# Puddles_Backplane_FOR_REFERENCE.net
KiCad netlist of a schematic drawn in EAGLE
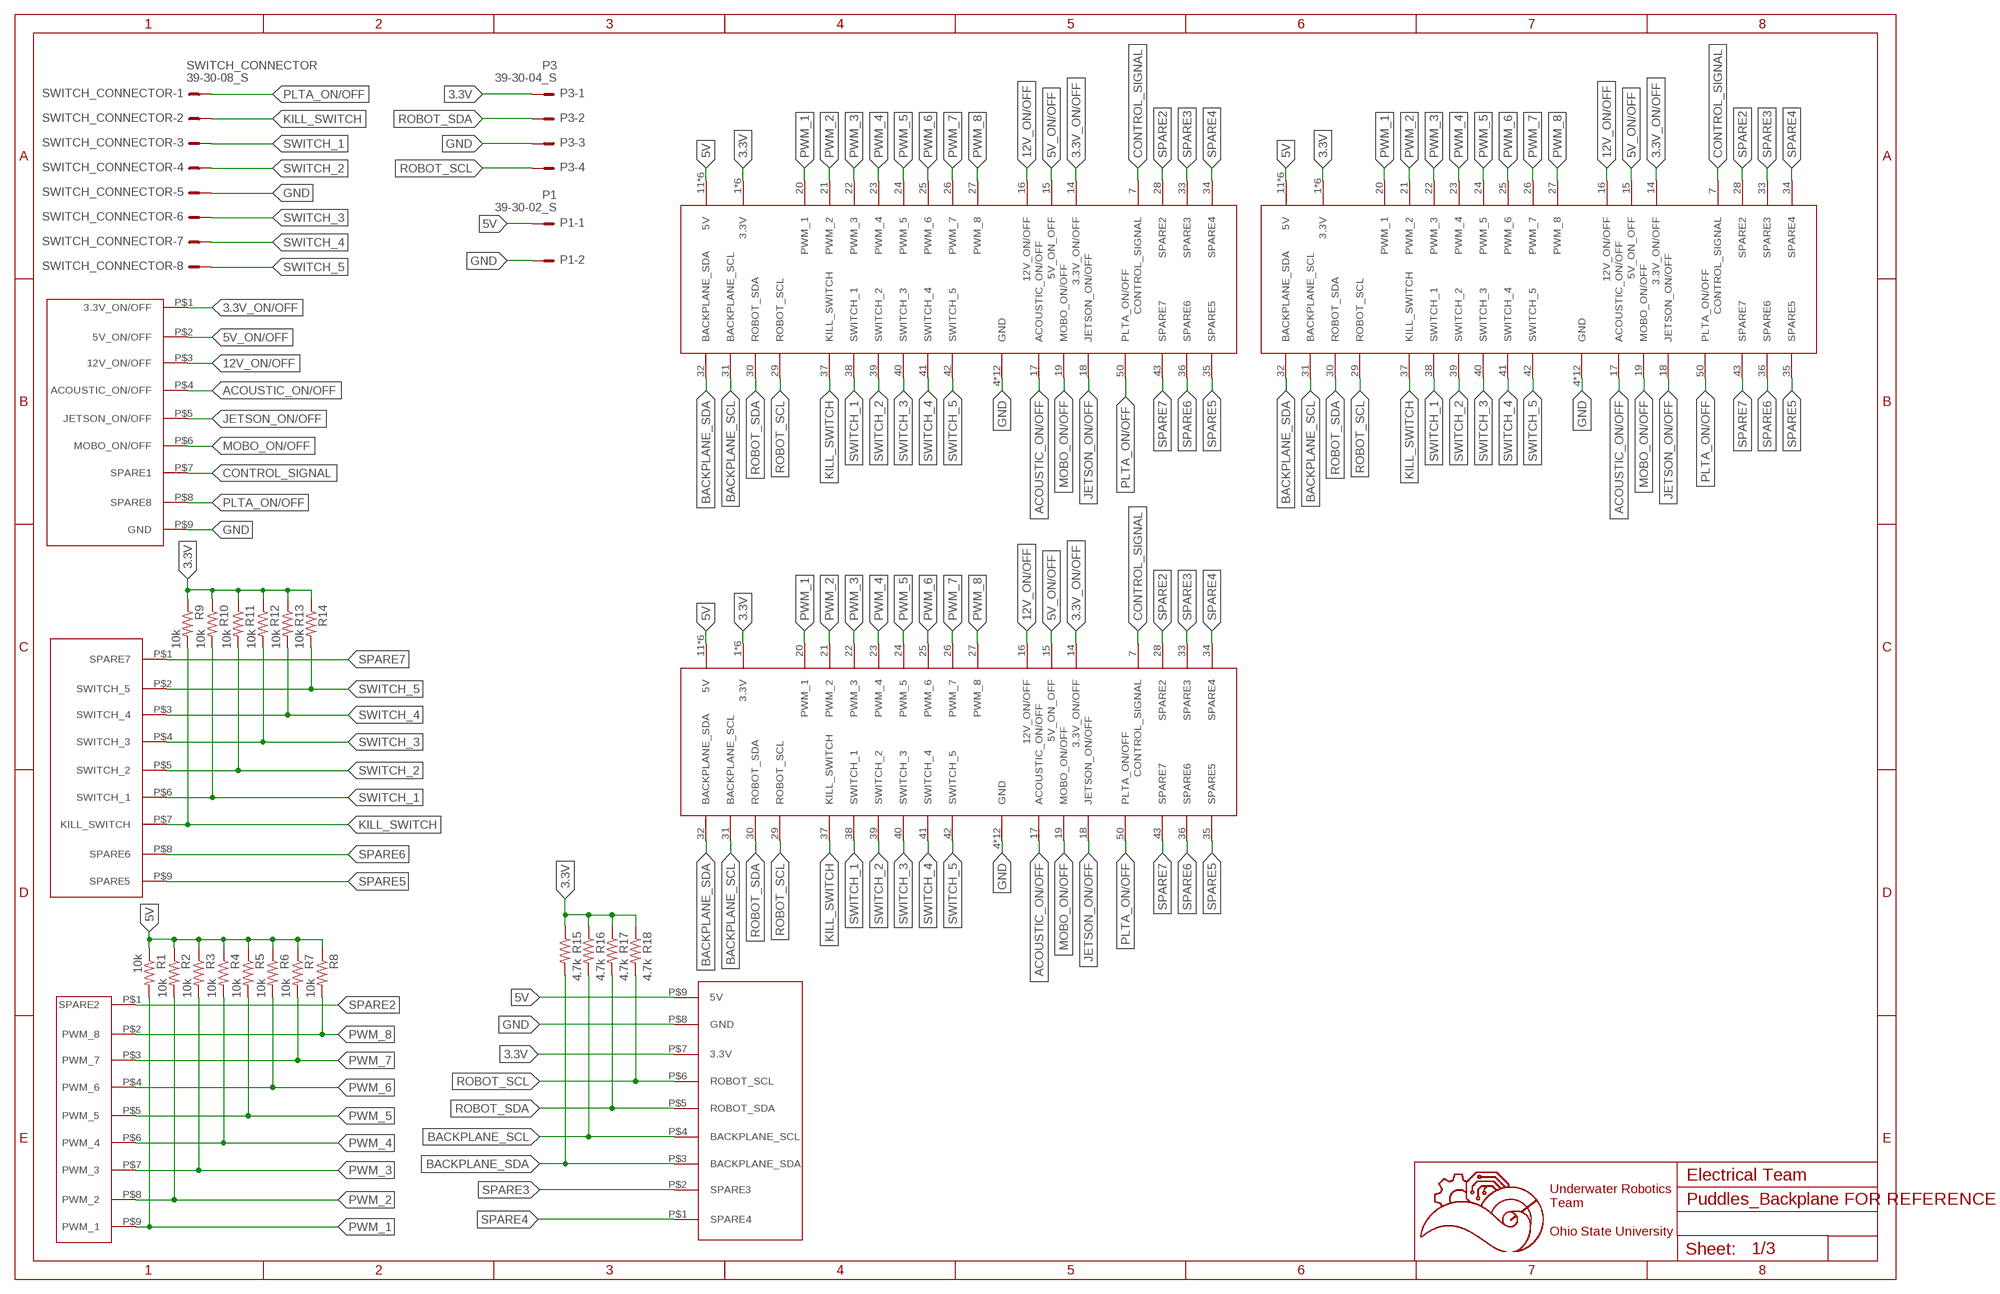
[diagram p0: schematic, sheet 1]
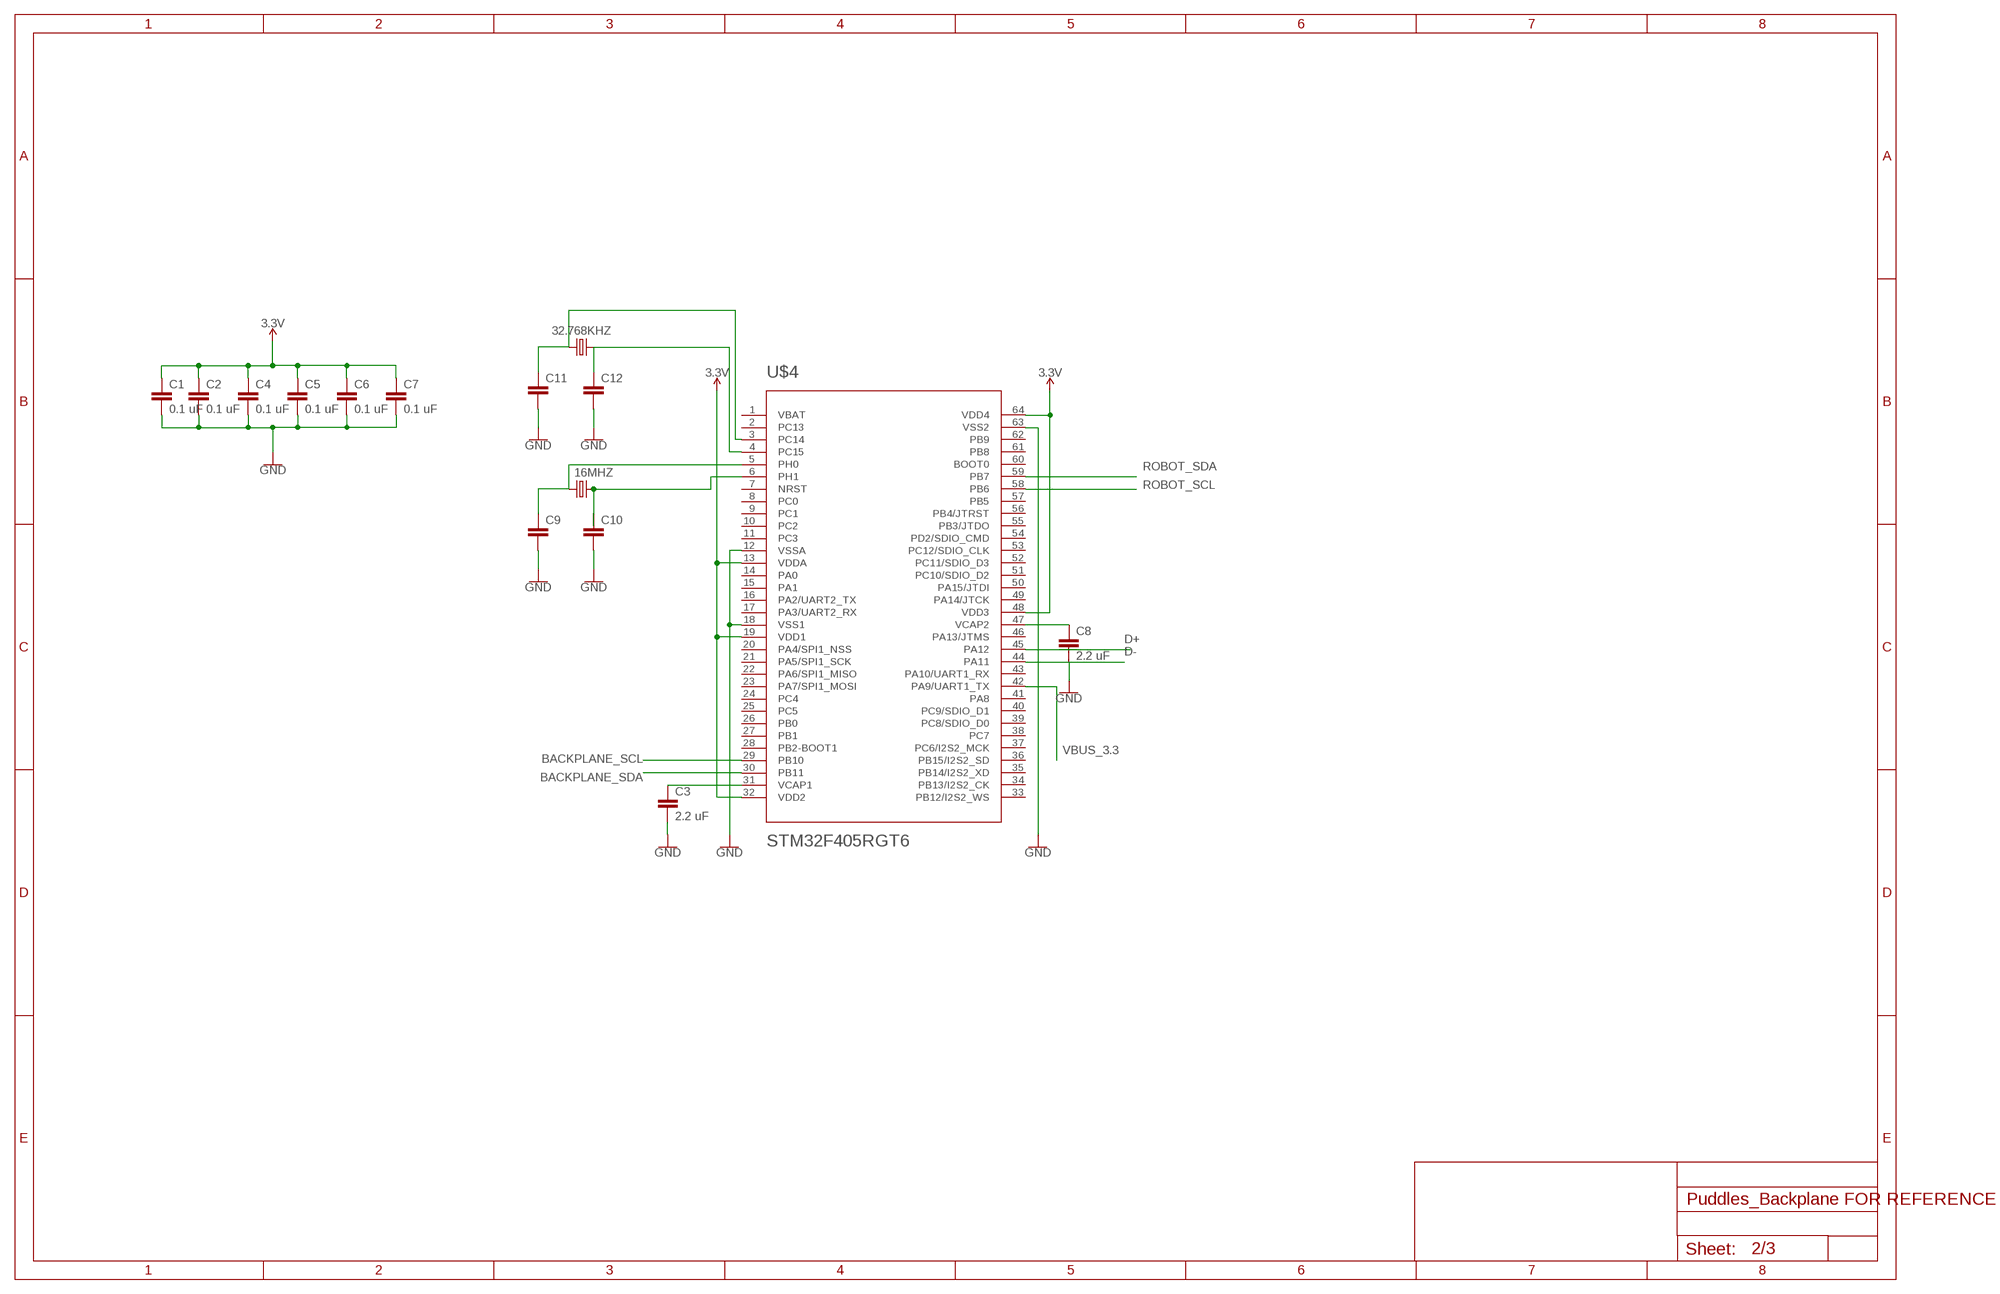
[diagram p1: schematic, sheet 2]
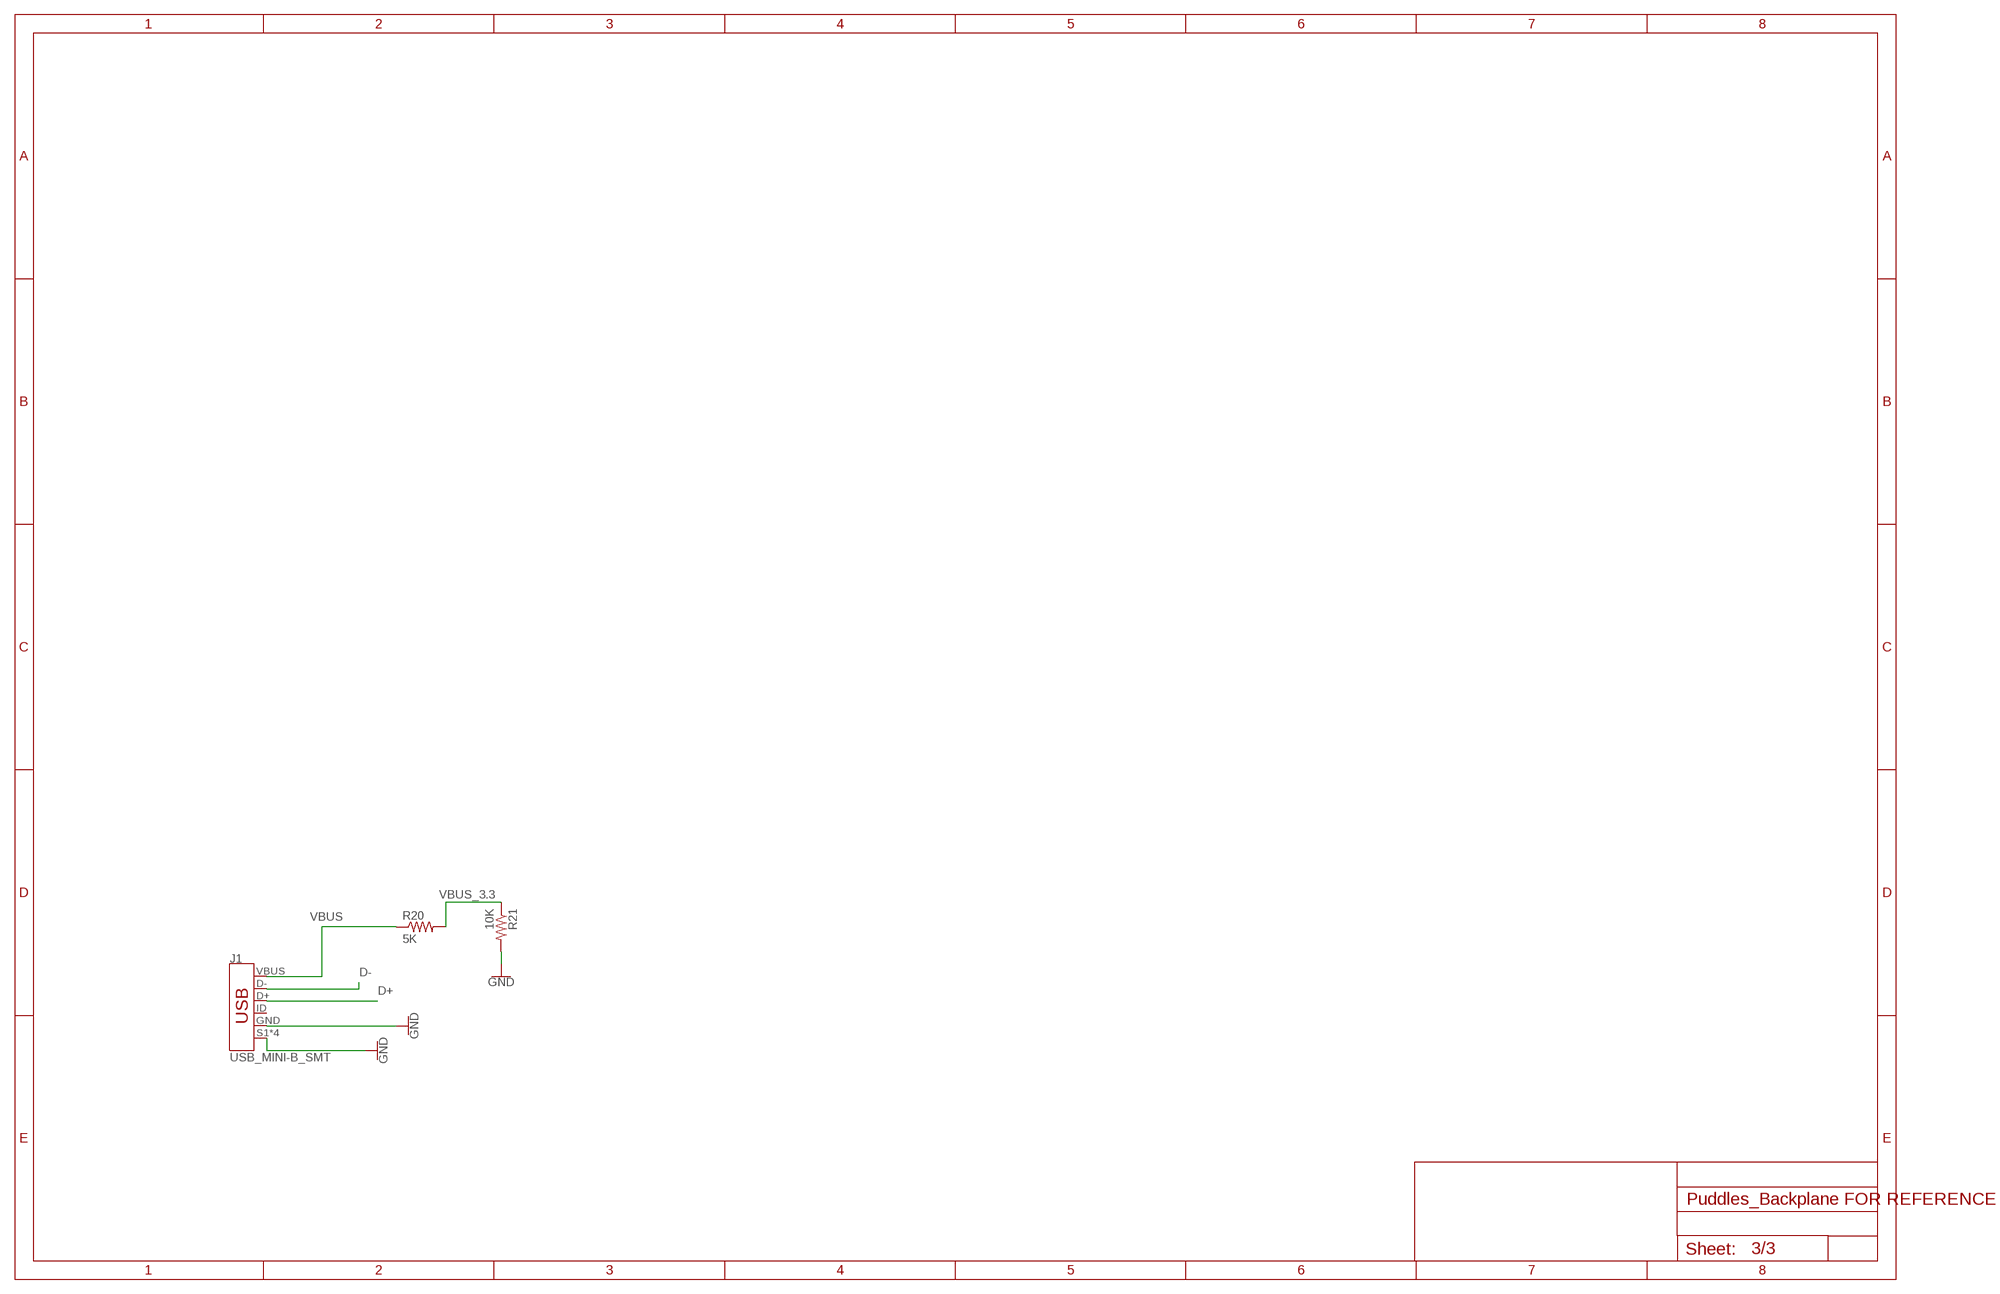
[diagram p2: schematic, sheet 3]

(export (version "E")
  (design (tool "Eeschema 10.0.6"))
  (components
    (comp (ref "J1")
      (value "USB_MINI-B_SMT")
      (footprint "eagle-import:USB-MINIB")
      (libsource (lib "eagle-import") (part "USB_MINI-B_SMT"))
    )
    (comp (ref "R20")
      (value "5K")
      (footprint "eagle-import:R0603")
      (libsource (lib "eagle-import") (part "R-US_R0603"))
    )
    (comp (ref "R21")
      (value "10K")
      (footprint "eagle-import:R0603")
      (libsource (lib "eagle-import") (part "R-US_R0603"))
    )
    (comp (ref "16MHZ")
      (value "CRYSTALPTH-HC49US")
      (footprint "eagle-import:HC49US")
      (libsource (lib "eagle-import") (part "CRYSTALPTH-HC49US"))
    )
    (comp (ref "32.768KHZ")
      (value "CRYSTALPTH-HC49US")
      (footprint "eagle-import:HC49US")
      (libsource (lib "eagle-import") (part "CRYSTALPTH-HC49US"))
    )
    (comp (ref "C1")
      (value "0.1 uF")
      (footprint "eagle-import:C0603")
      (libsource (lib "eagle-import") (part "C-EUC0603"))
    )
    (comp (ref "C2")
      (value "0.1 uF")
      (footprint "eagle-import:C0603")
      (libsource (lib "eagle-import") (part "C-EUC0603"))
    )
    (comp (ref "C3")
      (value "2.2 uF")
      (footprint "eagle-import:C0603")
      (libsource (lib "eagle-import") (part "C-EUC0603"))
    )
    (comp (ref "C4")
      (value "0.1 uF")
      (footprint "eagle-import:C0603")
      (libsource (lib "eagle-import") (part "C-EUC0603"))
    )
    (comp (ref "C5")
      (value "0.1 uF")
      (footprint "eagle-import:C0603")
      (libsource (lib "eagle-import") (part "C-EUC0603"))
    )
    (comp (ref "C6")
      (value "0.1 uF")
      (footprint "eagle-import:C0603")
      (libsource (lib "eagle-import") (part "C-EUC0603"))
    )
    (comp (ref "C7")
      (value "0.1 uF")
      (footprint "eagle-import:C0603")
      (libsource (lib "eagle-import") (part "C-EUC0603"))
    )
    (comp (ref "C8")
      (value "2.2 uF")
      (footprint "eagle-import:C0603")
      (libsource (lib "eagle-import") (part "C-EUC0603"))
    )
    (comp (ref "C9")
      (value "C-EUC0603")
      (footprint "eagle-import:C0603")
      (libsource (lib "eagle-import") (part "C-EUC0603"))
    )
    (comp (ref "C10")
      (value "C-EUC0603")
      (footprint "eagle-import:C0603")
      (libsource (lib "eagle-import") (part "C-EUC0603"))
    )
    (comp (ref "C11")
      (value "C-EUC0603")
      (footprint "eagle-import:C0603")
      (libsource (lib "eagle-import") (part "C-EUC0603"))
    )
    (comp (ref "C12")
      (value "C-EUC0603")
      (footprint "eagle-import:C0603")
      (libsource (lib "eagle-import") (part "C-EUC0603"))
    )
    (comp (ref "U$4")
      (value "STM32F405RGT6")
      (footprint "eagle-import:TQFP64")
      (libsource (lib "eagle-import") (part "STM32F405RG"))
    )
    (comp (ref "P1")
      (value "39-30-02_S")
      (footprint "eagle-import:39-30-_02_")
      (libsource (lib "eagle-import") (part "39-30-?02?_S"))
    )
    (comp (ref "P3")
      (value "39-30-04_S")
      (footprint "eagle-import:39-30-_04_")
      (libsource (lib "eagle-import") (part "39-30-?04?_S"))
    )
    (comp (ref "R1")
      (value "10k")
      (footprint "eagle-import:R0603")
      (libsource (lib "eagle-import") (part "R-US_R0603"))
    )
    (comp (ref "R2")
      (value "10k")
      (footprint "eagle-import:R0603")
      (libsource (lib "eagle-import") (part "R-US_R0603"))
    )
    (comp (ref "R3")
      (value "10k")
      (footprint "eagle-import:R0603")
      (libsource (lib "eagle-import") (part "R-US_R0603"))
    )
    (comp (ref "R4")
      (value "10k")
      (footprint "eagle-import:R0603")
      (libsource (lib "eagle-import") (part "R-US_R0603"))
    )
    (comp (ref "R5")
      (value "10k")
      (footprint "eagle-import:R0603")
      (libsource (lib "eagle-import") (part "R-US_R0603"))
    )
    (comp (ref "R6")
      (value "10k")
      (footprint "eagle-import:R0603")
      (libsource (lib "eagle-import") (part "R-US_R0603"))
    )
    (comp (ref "R7")
      (value "10k")
      (footprint "eagle-import:R0603")
      (libsource (lib "eagle-import") (part "R-US_R0603"))
    )
    (comp (ref "R8")
      (value "10k")
      (footprint "eagle-import:R0603")
      (libsource (lib "eagle-import") (part "R-US_R0603"))
    )
    (comp (ref "R9")
      (value "10k")
      (footprint "eagle-import:R0603")
      (libsource (lib "eagle-import") (part "R-US_R0603"))
    )
    (comp (ref "R10")
      (value "10k")
      (footprint "eagle-import:R0603")
      (libsource (lib "eagle-import") (part "R-US_R0603"))
    )
    (comp (ref "R11")
      (value "10k")
      (footprint "eagle-import:R0603")
      (libsource (lib "eagle-import") (part "R-US_R0603"))
    )
    (comp (ref "R12")
      (value "10k")
      (footprint "eagle-import:R0603")
      (libsource (lib "eagle-import") (part "R-US_R0603"))
    )
    (comp (ref "R13")
      (value "10k")
      (footprint "eagle-import:R0603")
      (libsource (lib "eagle-import") (part "R-US_R0603"))
    )
    (comp (ref "R14")
      (value "10k")
      (footprint "eagle-import:R0603")
      (libsource (lib "eagle-import") (part "R-US_R0603"))
    )
    (comp (ref "R15")
      (value "4.7k")
      (footprint "eagle-import:R0603")
      (libsource (lib "eagle-import") (part "R-US_R0603"))
    )
    (comp (ref "R16")
      (value "4.7k")
      (footprint "eagle-import:R0603")
      (libsource (lib "eagle-import") (part "R-US_R0603"))
    )
    (comp (ref "R17")
      (value "4.7k")
      (footprint "eagle-import:R0603")
      (libsource (lib "eagle-import") (part "R-US_R0603"))
    )
    (comp (ref "R18")
      (value "4.7k")
      (footprint "eagle-import:R0603")
      (libsource (lib "eagle-import") (part "R-US_R0603"))
    )
    (comp (ref "SWITCH_CONNECTOR")
      (value "39-30-08_S")
      (footprint "eagle-import:39-30-_08_")
      (libsource (lib "eagle-import") (part "39-30-?08?_S"))
    )
    (comp (ref "U$1")
      (value "5530843-FEMALE")
      (footprint "eagle-import:5530843-6-BACKPLANEMATE")
      (libsource (lib "eagle-import") (part "5530843-FEMALE"))
    )
    (comp (ref "U$2")
      (value "5530843-FEMALE")
      (footprint "eagle-import:5530843-6-BACKPLANEMATE")
      (libsource (lib "eagle-import") (part "5530843-FEMALE"))
    )
    (comp (ref "U$3")
      (value "5530843-FEMALE")
      (footprint "eagle-import:5530843-6-BACKPLANEMATE")
      (libsource (lib "eagle-import") (part "5530843-FEMALE"))
    )
    (comp (ref "U$5")
      (value "929870-01-09_1")
      (footprint "eagle-import:929852-01-09_1ROW")
      (libsource (lib "eagle-import") (part "929870-01-09_1"))
    )
    (comp (ref "U$6")
      (value "929870-01-09_2")
      (footprint "eagle-import:929852-01-09_1ROW")
      (libsource (lib "eagle-import") (part "929870-01-09_2"))
    )
    (comp (ref "U$7")
      (value "929870-01-09_3")
      (footprint "eagle-import:929852-01-09_1ROW")
      (libsource (lib "eagle-import") (part "929870-01-09_3"))
    )
    (comp (ref "U$8")
      (value "929870-01-09_4")
      (footprint "eagle-import:929852-01-09_1ROW")
      (libsource (lib "eagle-import") (part "929870-01-09_4"))
    )
  )
  (nets
    (net (code "1") (name "3.3V") (class "Default")
      (node (ref "C1") (pin "1") (pinfunction "1_1") (pintype "passive"))
      (node (ref "C2") (pin "1") (pinfunction "1_1") (pintype "passive"))
      (node (ref "C4") (pin "1") (pinfunction "1_1") (pintype "passive"))
      (node (ref "C5") (pin "1") (pinfunction "1_1") (pintype "passive"))
      (node (ref "C6") (pin "1") (pinfunction "1_1") (pintype "passive"))
      (node (ref "C7") (pin "1") (pinfunction "1_1") (pintype "passive"))
      (node (ref "P3") (pin "1") (pinfunction "P_1") (pintype "passive"))
      (node (ref "R10") (pin "1") (pinfunction "1_1") (pintype "passive"))
      (node (ref "R11") (pin "1") (pinfunction "1_1") (pintype "passive"))
      (node (ref "R12") (pin "1") (pinfunction "1_1") (pintype "passive"))
      (node (ref "R13") (pin "1") (pinfunction "1_1") (pintype "passive"))
      (node (ref "R14") (pin "1") (pinfunction "1_1") (pintype "passive"))
      (node (ref "R15") (pin "1") (pinfunction "1_1") (pintype "passive"))
      (node (ref "R16") (pin "1") (pinfunction "1_1") (pintype "passive"))
      (node (ref "R17") (pin "1") (pinfunction "1_1") (pintype "passive"))
      (node (ref "R18") (pin "1") (pinfunction "1_1") (pintype "passive"))
      (node (ref "R9") (pin "1") (pinfunction "1_1") (pintype "passive"))
      (node (ref "U$1") (pin "1") (pinfunction "3.3V_1") (pintype "bidirectional"))
      (node (ref "U$1") (pin "2") (pinfunction "3.3V_2") (pintype "bidirectional"))
      (node (ref "U$1") (pin "3") (pinfunction "3.3V_3") (pintype "bidirectional"))
      (node (ref "U$1") (pin "54") (pinfunction "3.3V_54") (pintype "bidirectional"))
      (node (ref "U$1") (pin "55") (pinfunction "3.3V_55") (pintype "bidirectional"))
      (node (ref "U$1") (pin "56") (pinfunction "3.3V_56") (pintype "bidirectional"))
      (node (ref "U$2") (pin "1") (pinfunction "3.3V_1") (pintype "bidirectional"))
      (node (ref "U$2") (pin "2") (pinfunction "3.3V_2") (pintype "bidirectional"))
      (node (ref "U$2") (pin "3") (pinfunction "3.3V_3") (pintype "bidirectional"))
      (node (ref "U$2") (pin "54") (pinfunction "3.3V_54") (pintype "bidirectional"))
      (node (ref "U$2") (pin "55") (pinfunction "3.3V_55") (pintype "bidirectional"))
      (node (ref "U$2") (pin "56") (pinfunction "3.3V_56") (pintype "bidirectional"))
      (node (ref "U$3") (pin "1") (pinfunction "3.3V_1") (pintype "bidirectional"))
      (node (ref "U$3") (pin "2") (pinfunction "3.3V_2") (pintype "bidirectional"))
      (node (ref "U$3") (pin "3") (pinfunction "3.3V_3") (pintype "bidirectional"))
      (node (ref "U$3") (pin "54") (pinfunction "3.3V_54") (pintype "bidirectional"))
      (node (ref "U$3") (pin "55") (pinfunction "3.3V_55") (pintype "bidirectional"))
      (node (ref "U$3") (pin "56") (pinfunction "3.3V_56") (pintype "bidirectional"))
      (node (ref "U$4") (pin "13") (pinfunction "VDDA_13") (pintype "bidirectional"))
      (node (ref "U$4") (pin "19") (pinfunction "VDD1_19") (pintype "bidirectional"))
      (node (ref "U$4") (pin "32") (pinfunction "VDD2_32") (pintype "bidirectional"))
      (node (ref "U$4") (pin "48") (pinfunction "VDD3_48") (pintype "bidirectional"))
      (node (ref "U$4") (pin "64") (pinfunction "VDD4_64") (pintype "bidirectional"))
      (node (ref "U$8") (pin "P$7") (pinfunction "3.3V_P$7") (pintype "bidirectional"))
    )
    (net (code "2") (name "3.3V_ON{slash}OFF") (class "Default")
      (node (ref "U$1") (pin "14") (pinfunction "3.3V_ON/OFF_14") (pintype "bidirectional"))
      (node (ref "U$2") (pin "14") (pinfunction "3.3V_ON/OFF_14") (pintype "bidirectional"))
      (node (ref "U$3") (pin "14") (pinfunction "3.3V_ON/OFF_14") (pintype "bidirectional"))
      (node (ref "U$7") (pin "P$1") (pinfunction "3.3V_ON/OFF_P$1") (pintype "bidirectional"))
    )
    (net (code "3") (name "5V") (class "Default")
      (node (ref "P1") (pin "1") (pinfunction "P_1") (pintype "passive"))
      (node (ref "R1") (pin "1") (pinfunction "1_1") (pintype "passive"))
      (node (ref "R2") (pin "1") (pinfunction "1_1") (pintype "passive"))
      (node (ref "R3") (pin "1") (pinfunction "1_1") (pintype "passive"))
      (node (ref "R4") (pin "1") (pinfunction "1_1") (pintype "passive"))
      (node (ref "R5") (pin "1") (pinfunction "1_1") (pintype "passive"))
      (node (ref "R6") (pin "1") (pinfunction "1_1") (pintype "passive"))
      (node (ref "R7") (pin "1") (pinfunction "1_1") (pintype "passive"))
      (node (ref "R8") (pin "1") (pinfunction "1_1") (pintype "passive"))
      (node (ref "U$1") (pin "11") (pinfunction "5V_11") (pintype "bidirectional"))
      (node (ref "U$1") (pin "12") (pinfunction "5V_12") (pintype "bidirectional"))
      (node (ref "U$1") (pin "13") (pinfunction "5V_13") (pintype "bidirectional"))
      (node (ref "U$1") (pin "44") (pinfunction "5V_44") (pintype "bidirectional"))
      (node (ref "U$1") (pin "45") (pinfunction "5V_45") (pintype "bidirectional"))
      (node (ref "U$1") (pin "46") (pinfunction "5V_46") (pintype "bidirectional"))
      (node (ref "U$2") (pin "11") (pinfunction "5V_11") (pintype "bidirectional"))
      (node (ref "U$2") (pin "12") (pinfunction "5V_12") (pintype "bidirectional"))
      (node (ref "U$2") (pin "13") (pinfunction "5V_13") (pintype "bidirectional"))
      (node (ref "U$2") (pin "44") (pinfunction "5V_44") (pintype "bidirectional"))
      (node (ref "U$2") (pin "45") (pinfunction "5V_45") (pintype "bidirectional"))
      (node (ref "U$2") (pin "46") (pinfunction "5V_46") (pintype "bidirectional"))
      (node (ref "U$3") (pin "11") (pinfunction "5V_11") (pintype "bidirectional"))
      (node (ref "U$3") (pin "12") (pinfunction "5V_12") (pintype "bidirectional"))
      (node (ref "U$3") (pin "13") (pinfunction "5V_13") (pintype "bidirectional"))
      (node (ref "U$3") (pin "44") (pinfunction "5V_44") (pintype "bidirectional"))
      (node (ref "U$3") (pin "45") (pinfunction "5V_45") (pintype "bidirectional"))
      (node (ref "U$3") (pin "46") (pinfunction "5V_46") (pintype "bidirectional"))
      (node (ref "U$8") (pin "P$9") (pinfunction "5V_P$9") (pintype "bidirectional"))
    )
    (net (code "4") (name "5V_ON{slash}OFF") (class "Default")
      (node (ref "U$1") (pin "15") (pinfunction "5V_ON_OFF_15") (pintype "bidirectional"))
      (node (ref "U$2") (pin "15") (pinfunction "5V_ON_OFF_15") (pintype "bidirectional"))
      (node (ref "U$3") (pin "15") (pinfunction "5V_ON_OFF_15") (pintype "bidirectional"))
      (node (ref "U$7") (pin "P$2") (pinfunction "5V_ON/OFF_P$2") (pintype "bidirectional"))
    )
    (net (code "5") (name "12V_ON{slash}OFF") (class "Default")
      (node (ref "U$1") (pin "16") (pinfunction "12V_ON/OFF_16") (pintype "bidirectional"))
      (node (ref "U$2") (pin "16") (pinfunction "12V_ON/OFF_16") (pintype "bidirectional"))
      (node (ref "U$3") (pin "16") (pinfunction "12V_ON/OFF_16") (pintype "bidirectional"))
      (node (ref "U$7") (pin "P$3") (pinfunction "12V_ON/OFF_P$3") (pintype "bidirectional"))
    )
    (net (code "6") (name "ACOUSTIC_ON{slash}OFF") (class "Default")
      (node (ref "U$1") (pin "17") (pinfunction "ACOUSTIC_ON/OFF_17") (pintype "bidirectional"))
      (node (ref "U$2") (pin "17") (pinfunction "ACOUSTIC_ON/OFF_17") (pintype "bidirectional"))
      (node (ref "U$3") (pin "17") (pinfunction "ACOUSTIC_ON/OFF_17") (pintype "bidirectional"))
      (node (ref "U$7") (pin "P$4") (pinfunction "ACOUSTIC_ON/OFF_P$4") (pintype "bidirectional"))
    )
    (net (code "7") (name "BACKPLANE_SCL") (class "Default")
      (node (ref "R16") (pin "2") (pinfunction "2_2") (pintype "passive"))
      (node (ref "U$1") (pin "31") (pinfunction "BACKPLANE_SCL_31") (pintype "bidirectional"))
      (node (ref "U$2") (pin "31") (pinfunction "BACKPLANE_SCL_31") (pintype "bidirectional"))
      (node (ref "U$3") (pin "31") (pinfunction "BACKPLANE_SCL_31") (pintype "bidirectional"))
      (node (ref "U$4") (pin "29") (pinfunction "PB10_29") (pintype "bidirectional"))
      (node (ref "U$8") (pin "P$4") (pinfunction "BACKPLANE_SCL_P$4") (pintype "bidirectional"))
    )
    (net (code "8") (name "BACKPLANE_SDA") (class "Default")
      (node (ref "R15") (pin "2") (pinfunction "2_2") (pintype "passive"))
      (node (ref "U$1") (pin "32") (pinfunction "BACKPLANE_SDA_32") (pintype "bidirectional"))
      (node (ref "U$2") (pin "32") (pinfunction "BACKPLANE_SDA_32") (pintype "bidirectional"))
      (node (ref "U$3") (pin "32") (pinfunction "BACKPLANE_SDA_32") (pintype "bidirectional"))
      (node (ref "U$4") (pin "30") (pinfunction "PB11_30") (pintype "bidirectional"))
      (node (ref "U$8") (pin "P$3") (pinfunction "BACKPLANE_SDA_P$3") (pintype "bidirectional"))
    )
    (net (code "9") (name "CONTROL_SIGNAL") (class "Default")
      (node (ref "U$1") (pin "7") (pinfunction "CONTROL_SIGNAL_7") (pintype "bidirectional"))
      (node (ref "U$2") (pin "7") (pinfunction "CONTROL_SIGNAL_7") (pintype "bidirectional"))
      (node (ref "U$3") (pin "7") (pinfunction "CONTROL_SIGNAL_7") (pintype "bidirectional"))
      (node (ref "U$7") (pin "P$7") (pinfunction "SPARE1_P$7") (pintype "bidirectional"))
    )
    (net (code "10") (name "D+") (class "Default")
      (node (ref "J1") (pin "D+") (pinfunction "D+_D+") (pintype "bidirectional"))
      (node (ref "U$4") (pin "45") (pinfunction "PA12_45") (pintype "bidirectional"))
    )
    (net (code "11") (name "D-") (class "Default")
      (node (ref "J1") (pin "D-") (pinfunction "D-_D-") (pintype "bidirectional"))
      (node (ref "U$4") (pin "44") (pinfunction "PA11_44") (pintype "bidirectional"))
    )
    (net (code "12") (name "GND") (class "Default")
      (node (ref "C1") (pin "2") (pinfunction "2_2") (pintype "passive"))
      (node (ref "C10") (pin "2") (pinfunction "2_2") (pintype "passive"))
      (node (ref "C11") (pin "2") (pinfunction "2_2") (pintype "passive"))
      (node (ref "C12") (pin "2") (pinfunction "2_2") (pintype "passive"))
      (node (ref "C2") (pin "2") (pinfunction "2_2") (pintype "passive"))
      (node (ref "C3") (pin "2") (pinfunction "2_2") (pintype "passive"))
      (node (ref "C4") (pin "2") (pinfunction "2_2") (pintype "passive"))
      (node (ref "C5") (pin "2") (pinfunction "2_2") (pintype "passive"))
      (node (ref "C6") (pin "2") (pinfunction "2_2") (pintype "passive"))
      (node (ref "C7") (pin "2") (pinfunction "2_2") (pintype "passive"))
      (node (ref "C8") (pin "2") (pinfunction "2_2") (pintype "passive"))
      (node (ref "C9") (pin "2") (pinfunction "2_2") (pintype "passive"))
      (node (ref "J1") (pin "GND") (pinfunction "GND_GND") (pintype "power_in"))
      (node (ref "J1") (pin "S1") (pinfunction "SHIELD_S1") (pintype "bidirectional"))
      (node (ref "J1") (pin "S2") (pinfunction "SHIELD_S2") (pintype "bidirectional"))
      (node (ref "J1") (pin "S3") (pinfunction "SHIELD_S3") (pintype "bidirectional"))
      (node (ref "J1") (pin "S4") (pinfunction "SHIELD_S4") (pintype "bidirectional"))
      (node (ref "P1") (pin "2") (pinfunction "P_2") (pintype "passive"))
      (node (ref "P3") (pin "3") (pinfunction "P_3") (pintype "passive"))
      (node (ref "R21") (pin "2") (pinfunction "2_2") (pintype "passive"))
      (node (ref "SWITCH_CONNECTOR") (pin "5") (pinfunction "P_5") (pintype "passive"))
      (node (ref "U$1") (pin "10") (pinfunction "GND_10") (pintype "bidirectional"))
      (node (ref "U$1") (pin "4") (pinfunction "GND_4") (pintype "bidirectional"))
      (node (ref "U$1") (pin "47") (pinfunction "GND_47") (pintype "bidirectional"))
      (node (ref "U$1") (pin "48") (pinfunction "GND_48") (pintype "bidirectional"))
      (node (ref "U$1") (pin "49") (pinfunction "GND_49") (pintype "bidirectional"))
      (node (ref "U$1") (pin "5") (pinfunction "GND_5") (pintype "bidirectional"))
      (node (ref "U$1") (pin "51") (pinfunction "GND_51") (pintype "bidirectional"))
      (node (ref "U$1") (pin "52") (pinfunction "GND_52") (pintype "bidirectional"))
      (node (ref "U$1") (pin "53") (pinfunction "GND_53") (pintype "bidirectional"))
      (node (ref "U$1") (pin "6") (pinfunction "GND_6") (pintype "bidirectional"))
      (node (ref "U$1") (pin "8") (pinfunction "GND_8") (pintype "bidirectional"))
      (node (ref "U$1") (pin "9") (pinfunction "GND_9") (pintype "bidirectional"))
      (node (ref "U$2") (pin "10") (pinfunction "GND_10") (pintype "bidirectional"))
      (node (ref "U$2") (pin "4") (pinfunction "GND_4") (pintype "bidirectional"))
      (node (ref "U$2") (pin "47") (pinfunction "GND_47") (pintype "bidirectional"))
      (node (ref "U$2") (pin "48") (pinfunction "GND_48") (pintype "bidirectional"))
      (node (ref "U$2") (pin "49") (pinfunction "GND_49") (pintype "bidirectional"))
      (node (ref "U$2") (pin "5") (pinfunction "GND_5") (pintype "bidirectional"))
      (node (ref "U$2") (pin "51") (pinfunction "GND_51") (pintype "bidirectional"))
      (node (ref "U$2") (pin "52") (pinfunction "GND_52") (pintype "bidirectional"))
      (node (ref "U$2") (pin "53") (pinfunction "GND_53") (pintype "bidirectional"))
      (node (ref "U$2") (pin "6") (pinfunction "GND_6") (pintype "bidirectional"))
      (node (ref "U$2") (pin "8") (pinfunction "GND_8") (pintype "bidirectional"))
      (node (ref "U$2") (pin "9") (pinfunction "GND_9") (pintype "bidirectional"))
      (node (ref "U$3") (pin "10") (pinfunction "GND_10") (pintype "bidirectional"))
      (node (ref "U$3") (pin "4") (pinfunction "GND_4") (pintype "bidirectional"))
      (node (ref "U$3") (pin "47") (pinfunction "GND_47") (pintype "bidirectional"))
      (node (ref "U$3") (pin "48") (pinfunction "GND_48") (pintype "bidirectional"))
      (node (ref "U$3") (pin "49") (pinfunction "GND_49") (pintype "bidirectional"))
      (node (ref "U$3") (pin "5") (pinfunction "GND_5") (pintype "bidirectional"))
      (node (ref "U$3") (pin "51") (pinfunction "GND_51") (pintype "bidirectional"))
      (node (ref "U$3") (pin "52") (pinfunction "GND_52") (pintype "bidirectional"))
      (node (ref "U$3") (pin "53") (pinfunction "GND_53") (pintype "bidirectional"))
      (node (ref "U$3") (pin "6") (pinfunction "GND_6") (pintype "bidirectional"))
      (node (ref "U$3") (pin "8") (pinfunction "GND_8") (pintype "bidirectional"))
      (node (ref "U$3") (pin "9") (pinfunction "GND_9") (pintype "bidirectional"))
      (node (ref "U$4") (pin "12") (pinfunction "VSSA_12") (pintype "bidirectional"))
      (node (ref "U$4") (pin "18") (pinfunction "VSS1_18") (pintype "bidirectional"))
      (node (ref "U$4") (pin "63") (pinfunction "VSS2_63") (pintype "bidirectional"))
      (node (ref "U$7") (pin "P$9") (pinfunction "GND_P$9") (pintype "bidirectional"))
      (node (ref "U$8") (pin "P$8") (pinfunction "GND_P$8") (pintype "bidirectional"))
    )
    (net (code "13") (name "JETSON_ON{slash}OFF") (class "Default")
      (node (ref "U$1") (pin "18") (pinfunction "JETSON_ON/OFF_18") (pintype "bidirectional"))
      (node (ref "U$2") (pin "18") (pinfunction "JETSON_ON/OFF_18") (pintype "bidirectional"))
      (node (ref "U$3") (pin "18") (pinfunction "JETSON_ON/OFF_18") (pintype "bidirectional"))
      (node (ref "U$7") (pin "P$5") (pinfunction "JETSON_ON/OFF_P$5") (pintype "bidirectional"))
    )
    (net (code "14") (name "KILL_SWITCH") (class "Default")
      (node (ref "R9") (pin "2") (pinfunction "2_2") (pintype "passive"))
      (node (ref "SWITCH_CONNECTOR") (pin "2") (pinfunction "P_2") (pintype "passive"))
      (node (ref "U$1") (pin "37") (pinfunction "KILL_SWITCH_37") (pintype "output"))
      (node (ref "U$2") (pin "37") (pinfunction "KILL_SWITCH_37") (pintype "output"))
      (node (ref "U$3") (pin "37") (pinfunction "KILL_SWITCH_37") (pintype "output"))
      (node (ref "U$5") (pin "P$7") (pinfunction "KILL_SWITCH_P$7") (pintype "bidirectional"))
    )
    (net (code "15") (name "MOBO_ON{slash}OFF") (class "Default")
      (node (ref "U$1") (pin "19") (pinfunction "MOBO_ON/OFF_19") (pintype "bidirectional"))
      (node (ref "U$2") (pin "19") (pinfunction "MOBO_ON/OFF_19") (pintype "bidirectional"))
      (node (ref "U$3") (pin "19") (pinfunction "MOBO_ON/OFF_19") (pintype "bidirectional"))
      (node (ref "U$7") (pin "P$6") (pinfunction "MOBO_ON/OFF_P$6") (pintype "bidirectional"))
    )
    (net (code "16") (name "Net-(U$4-PC14)") (class "Default")
      (node (ref "32.768KHZ") (pin "1") (pinfunction "1_1") (pintype "passive"))
      (node (ref "C11") (pin "1") (pinfunction "1_1") (pintype "passive"))
      (node (ref "U$4") (pin "3") (pinfunction "PC14_3") (pintype "bidirectional"))
    )
    (net (code "17") (name "Net-(U$4-PC15)") (class "Default")
      (node (ref "32.768KHZ") (pin "2") (pinfunction "2_2") (pintype "passive"))
      (node (ref "C12") (pin "1") (pinfunction "1_1") (pintype "passive"))
      (node (ref "U$4") (pin "4") (pinfunction "PC15_4") (pintype "bidirectional"))
    )
    (net (code "18") (name "Net-(U$4-PH0)") (class "Default")
      (node (ref "16MHZ") (pin "1") (pinfunction "1_1") (pintype "passive"))
      (node (ref "C9") (pin "1") (pinfunction "1_1") (pintype "passive"))
      (node (ref "U$4") (pin "5") (pinfunction "PH0_5") (pintype "bidirectional"))
    )
    (net (code "19") (name "Net-(U$4-PH1)") (class "Default")
      (node (ref "16MHZ") (pin "2") (pinfunction "2_2") (pintype "passive"))
      (node (ref "C10") (pin "1") (pinfunction "1_1") (pintype "passive"))
      (node (ref "U$4") (pin "6") (pinfunction "PH1_6") (pintype "bidirectional"))
    )
    (net (code "20") (name "Net-(U$4-VCAP1)") (class "Default")
      (node (ref "C3") (pin "1") (pinfunction "1_1") (pintype "passive"))
      (node (ref "U$4") (pin "31") (pinfunction "VCAP1_31") (pintype "bidirectional"))
    )
    (net (code "21") (name "Net-(U$4-VCAP2)") (class "Default")
      (node (ref "C8") (pin "1") (pinfunction "1_1") (pintype "passive"))
      (node (ref "U$4") (pin "47") (pinfunction "VCAP2_47") (pintype "bidirectional"))
    )
    (net (code "22") (name "PLTA_ON{slash}OFF") (class "Default")
      (node (ref "SWITCH_CONNECTOR") (pin "1") (pinfunction "P_1") (pintype "passive"))
      (node (ref "U$1") (pin "50") (pinfunction "PLTA_ON/OFF_50") (pintype "bidirectional"))
      (node (ref "U$2") (pin "50") (pinfunction "PLTA_ON/OFF_50") (pintype "bidirectional"))
      (node (ref "U$3") (pin "50") (pinfunction "PLTA_ON/OFF_50") (pintype "bidirectional"))
      (node (ref "U$7") (pin "P$8") (pinfunction "SPARE8_P$8") (pintype "bidirectional"))
    )
    (net (code "23") (name "PWM_1") (class "Default")
      (node (ref "R1") (pin "2") (pinfunction "2_2") (pintype "passive"))
      (node (ref "U$1") (pin "20") (pinfunction "PWM_1_20") (pintype "bidirectional"))
      (node (ref "U$2") (pin "20") (pinfunction "PWM_1_20") (pintype "bidirectional"))
      (node (ref "U$3") (pin "20") (pinfunction "PWM_1_20") (pintype "bidirectional"))
      (node (ref "U$6") (pin "P$9") (pinfunction "PWM_1_P$9") (pintype "bidirectional"))
    )
    (net (code "24") (name "PWM_2") (class "Default")
      (node (ref "R2") (pin "2") (pinfunction "2_2") (pintype "passive"))
      (node (ref "U$1") (pin "21") (pinfunction "PWM_2_21") (pintype "bidirectional"))
      (node (ref "U$2") (pin "21") (pinfunction "PWM_2_21") (pintype "bidirectional"))
      (node (ref "U$3") (pin "21") (pinfunction "PWM_2_21") (pintype "bidirectional"))
      (node (ref "U$6") (pin "P$8") (pinfunction "PWM_2_P$8") (pintype "bidirectional"))
    )
    (net (code "25") (name "PWM_3") (class "Default")
      (node (ref "R3") (pin "2") (pinfunction "2_2") (pintype "passive"))
      (node (ref "U$1") (pin "22") (pinfunction "PWM_3_22") (pintype "bidirectional"))
      (node (ref "U$2") (pin "22") (pinfunction "PWM_3_22") (pintype "bidirectional"))
      (node (ref "U$3") (pin "22") (pinfunction "PWM_3_22") (pintype "bidirectional"))
      (node (ref "U$6") (pin "P$7") (pinfunction "PWM_3_P$7") (pintype "bidirectional"))
    )
    (net (code "26") (name "PWM_4") (class "Default")
      (node (ref "R4") (pin "2") (pinfunction "2_2") (pintype "passive"))
      (node (ref "U$1") (pin "23") (pinfunction "PWM_4_23") (pintype "bidirectional"))
      (node (ref "U$2") (pin "23") (pinfunction "PWM_4_23") (pintype "bidirectional"))
      (node (ref "U$3") (pin "23") (pinfunction "PWM_4_23") (pintype "bidirectional"))
      (node (ref "U$6") (pin "P$6") (pinfunction "PWM_4_P$6") (pintype "bidirectional"))
    )
    (net (code "27") (name "PWM_5") (class "Default")
      (node (ref "R5") (pin "2") (pinfunction "2_2") (pintype "passive"))
      (node (ref "U$1") (pin "24") (pinfunction "PWM_5_24") (pintype "bidirectional"))
      (node (ref "U$2") (pin "24") (pinfunction "PWM_5_24") (pintype "bidirectional"))
      (node (ref "U$3") (pin "24") (pinfunction "PWM_5_24") (pintype "bidirectional"))
      (node (ref "U$6") (pin "P$5") (pinfunction "PWM_5_P$5") (pintype "bidirectional"))
    )
    (net (code "28") (name "PWM_6") (class "Default")
      (node (ref "R6") (pin "2") (pinfunction "2_2") (pintype "passive"))
      (node (ref "U$1") (pin "25") (pinfunction "PWM_6_25") (pintype "bidirectional"))
      (node (ref "U$2") (pin "25") (pinfunction "PWM_6_25") (pintype "bidirectional"))
      (node (ref "U$3") (pin "25") (pinfunction "PWM_6_25") (pintype "bidirectional"))
      (node (ref "U$6") (pin "P$4") (pinfunction "PWM_6_P$4") (pintype "bidirectional"))
    )
    (net (code "29") (name "PWM_7") (class "Default")
      (node (ref "R7") (pin "2") (pinfunction "2_2") (pintype "passive"))
      (node (ref "U$1") (pin "26") (pinfunction "PWM_7_26") (pintype "bidirectional"))
      (node (ref "U$2") (pin "26") (pinfunction "PWM_7_26") (pintype "bidirectional"))
      (node (ref "U$3") (pin "26") (pinfunction "PWM_7_26") (pintype "bidirectional"))
      (node (ref "U$6") (pin "P$3") (pinfunction "PWM_7_P$3") (pintype "bidirectional"))
    )
    (net (code "30") (name "PWM_8") (class "Default")
      (node (ref "R8") (pin "2") (pinfunction "2_2") (pintype "passive"))
      (node (ref "U$1") (pin "27") (pinfunction "PWM_8_27") (pintype "bidirectional"))
      (node (ref "U$2") (pin "27") (pinfunction "PWM_8_27") (pintype "bidirectional"))
      (node (ref "U$3") (pin "27") (pinfunction "PWM_8_27") (pintype "bidirectional"))
      (node (ref "U$6") (pin "P$2") (pinfunction "PWM_8_P$2") (pintype "bidirectional"))
    )
    (net (code "31") (name "ROBOT_SCL") (class "Default")
      (node (ref "P3") (pin "4") (pinfunction "P_4") (pintype "passive"))
      (node (ref "R18") (pin "2") (pinfunction "2_2") (pintype "passive"))
      (node (ref "U$1") (pin "29") (pinfunction "ROBOT_SCL_29") (pintype "bidirectional"))
      (node (ref "U$2") (pin "29") (pinfunction "ROBOT_SCL_29") (pintype "bidirectional"))
      (node (ref "U$3") (pin "29") (pinfunction "ROBOT_SCL_29") (pintype "bidirectional"))
      (node (ref "U$4") (pin "58") (pinfunction "PB6_58") (pintype "bidirectional"))
      (node (ref "U$8") (pin "P$6") (pinfunction "ROBOT_SCL_P$6") (pintype "bidirectional"))
    )
    (net (code "32") (name "ROBOT_SDA") (class "Default")
      (node (ref "P3") (pin "2") (pinfunction "P_2") (pintype "passive"))
      (node (ref "R17") (pin "2") (pinfunction "2_2") (pintype "passive"))
      (node (ref "U$1") (pin "30") (pinfunction "ROBOT_SDA_30") (pintype "bidirectional"))
      (node (ref "U$2") (pin "30") (pinfunction "ROBOT_SDA_30") (pintype "bidirectional"))
      (node (ref "U$3") (pin "30") (pinfunction "ROBOT_SDA_30") (pintype "bidirectional"))
      (node (ref "U$4") (pin "59") (pinfunction "PB7_59") (pintype "bidirectional"))
      (node (ref "U$8") (pin "P$5") (pinfunction "ROBOT_SDA_P$5") (pintype "bidirectional"))
    )
    (net (code "33") (name "SPARE2") (class "Default")
      (node (ref "U$1") (pin "28") (pinfunction "SPARE2_28") (pintype "bidirectional"))
      (node (ref "U$2") (pin "28") (pinfunction "SPARE2_28") (pintype "bidirectional"))
      (node (ref "U$3") (pin "28") (pinfunction "SPARE2_28") (pintype "bidirectional"))
      (node (ref "U$6") (pin "P$1") (pinfunction "SPARE2_P$1") (pintype "bidirectional"))
    )
    (net (code "34") (name "SPARE3") (class "Default")
      (node (ref "U$1") (pin "33") (pinfunction "SPARE3_33") (pintype "bidirectional"))
      (node (ref "U$2") (pin "33") (pinfunction "SPARE3_33") (pintype "bidirectional"))
      (node (ref "U$3") (pin "33") (pinfunction "SPARE3_33") (pintype "bidirectional"))
      (node (ref "U$8") (pin "P$2") (pinfunction "SPARE3_P$2") (pintype "bidirectional"))
    )
    (net (code "35") (name "SPARE4") (class "Default")
      (node (ref "U$1") (pin "34") (pinfunction "SPARE4_34") (pintype "bidirectional"))
      (node (ref "U$2") (pin "34") (pinfunction "SPARE4_34") (pintype "bidirectional"))
      (node (ref "U$3") (pin "34") (pinfunction "SPARE4_34") (pintype "bidirectional"))
      (node (ref "U$8") (pin "P$1") (pinfunction "SPARE4_P$1") (pintype "bidirectional"))
    )
    (net (code "36") (name "SPARE5") (class "Default")
      (node (ref "U$1") (pin "35") (pinfunction "SPARE5_35") (pintype "bidirectional"))
      (node (ref "U$2") (pin "35") (pinfunction "SPARE5_35") (pintype "bidirectional"))
      (node (ref "U$3") (pin "35") (pinfunction "SPARE5_35") (pintype "bidirectional"))
      (node (ref "U$5") (pin "P$9") (pinfunction "SPARE5_P$9") (pintype "bidirectional"))
    )
    (net (code "37") (name "SPARE6") (class "Default")
      (node (ref "U$1") (pin "36") (pinfunction "SPARE6_36") (pintype "bidirectional"))
      (node (ref "U$2") (pin "36") (pinfunction "SPARE6_36") (pintype "bidirectional"))
      (node (ref "U$3") (pin "36") (pinfunction "SPARE6_36") (pintype "bidirectional"))
      (node (ref "U$5") (pin "P$8") (pinfunction "SPARE6_P$8") (pintype "bidirectional"))
    )
    (net (code "38") (name "SPARE7") (class "Default")
      (node (ref "U$1") (pin "43") (pinfunction "SPARE7_43") (pintype "bidirectional"))
      (node (ref "U$2") (pin "43") (pinfunction "SPARE7_43") (pintype "bidirectional"))
      (node (ref "U$3") (pin "43") (pinfunction "SPARE7_43") (pintype "bidirectional"))
      (node (ref "U$5") (pin "P$1") (pinfunction "SPARE7_P$1") (pintype "bidirectional"))
    )
    (net (code "39") (name "SWITCH_1") (class "Default")
      (node (ref "R10") (pin "2") (pinfunction "2_2") (pintype "passive"))
      (node (ref "SWITCH_CONNECTOR") (pin "3") (pinfunction "P_3") (pintype "passive"))
      (node (ref "U$1") (pin "38") (pinfunction "SWITCH_1_38") (pintype "output"))
      (node (ref "U$2") (pin "38") (pinfunction "SWITCH_1_38") (pintype "output"))
      (node (ref "U$3") (pin "38") (pinfunction "SWITCH_1_38") (pintype "output"))
      (node (ref "U$5") (pin "P$6") (pinfunction "SWITCH_1_P$6") (pintype "bidirectional"))
    )
    (net (code "40") (name "SWITCH_2") (class "Default")
      (node (ref "R11") (pin "2") (pinfunction "2_2") (pintype "passive"))
      (node (ref "SWITCH_CONNECTOR") (pin "4") (pinfunction "P_4") (pintype "passive"))
      (node (ref "U$1") (pin "39") (pinfunction "SWITCH_2_39") (pintype "output"))
      (node (ref "U$2") (pin "39") (pinfunction "SWITCH_2_39") (pintype "output"))
      (node (ref "U$3") (pin "39") (pinfunction "SWITCH_2_39") (pintype "output"))
      (node (ref "U$5") (pin "P$5") (pinfunction "SWITCH_2_P$5") (pintype "bidirectional"))
    )
    (net (code "41") (name "SWITCH_3") (class "Default")
      (node (ref "R12") (pin "2") (pinfunction "2_2") (pintype "passive"))
      (node (ref "SWITCH_CONNECTOR") (pin "6") (pinfunction "P_6") (pintype "passive"))
      (node (ref "U$1") (pin "40") (pinfunction "SWITCH_3_40") (pintype "output"))
      (node (ref "U$2") (pin "40") (pinfunction "SWITCH_3_40") (pintype "output"))
      (node (ref "U$3") (pin "40") (pinfunction "SWITCH_3_40") (pintype "output"))
      (node (ref "U$5") (pin "P$4") (pinfunction "SWITCH_3_P$4") (pintype "bidirectional"))
    )
    (net (code "42") (name "SWITCH_4") (class "Default")
      (node (ref "R13") (pin "2") (pinfunction "2_2") (pintype "passive"))
      (node (ref "SWITCH_CONNECTOR") (pin "7") (pinfunction "P_7") (pintype "passive"))
      (node (ref "U$1") (pin "41") (pinfunction "SWITCH_4_41") (pintype "output"))
      (node (ref "U$2") (pin "41") (pinfunction "SWITCH_4_41") (pintype "output"))
      (node (ref "U$3") (pin "41") (pinfunction "SWITCH_4_41") (pintype "output"))
      (node (ref "U$5") (pin "P$3") (pinfunction "SWITCH_4_P$3") (pintype "bidirectional"))
    )
    (net (code "43") (name "SWITCH_5") (class "Default")
      (node (ref "R14") (pin "2") (pinfunction "2_2") (pintype "passive"))
      (node (ref "SWITCH_CONNECTOR") (pin "8") (pinfunction "P_8") (pintype "passive"))
      (node (ref "U$1") (pin "42") (pinfunction "SWITCH_5_42") (pintype "output"))
      (node (ref "U$2") (pin "42") (pinfunction "SWITCH_5_42") (pintype "output"))
      (node (ref "U$3") (pin "42") (pinfunction "SWITCH_5_42") (pintype "output"))
      (node (ref "U$5") (pin "P$2") (pinfunction "SWITCH_5_P$2") (pintype "bidirectional"))
    )
    (net (code "44") (name "VBUS") (class "Default")
      (node (ref "J1") (pin "VBUS") (pinfunction "VBUS_VBUS") (pintype "power_in"))
      (node (ref "R20") (pin "1") (pinfunction "1_1") (pintype "passive"))
    )
    (net (code "45") (name "VBUS_3.3") (class "Default")
      (node (ref "R20") (pin "2") (pinfunction "2_2") (pintype "passive"))
      (node (ref "R21") (pin "1") (pinfunction "1_1") (pintype "passive"))
      (node (ref "U$4") (pin "42") (pinfunction "PA9/UART1_TX_42") (pintype "bidirectional"))
    )
    (net (code "46") (name "unconnected-(J1-PadID)") (class "Default")
      (node (ref "J1") (pin "ID") (pinfunction "ID_ID") (pintype "bidirectional"))
    )
    (net (code "47") (name "unconnected-(U$4-BOOT0-Pad60)") (class "Default")
      (node (ref "U$4") (pin "60") (pinfunction "BOOT0_60") (pintype "bidirectional"))
    )
    (net (code "48") (name "unconnected-(U$4-NRST-Pad7)") (class "Default")
      (node (ref "U$4") (pin "7") (pinfunction "NRST_7") (pintype "bidirectional"))
    )
    (net (code "49") (name "unconnected-(U$4-PA0-Pad14)") (class "Default")
      (node (ref "U$4") (pin "14") (pinfunction "PA0_14") (pintype "bidirectional"))
    )
    (net (code "50") (name "unconnected-(U$4-PA1-Pad15)") (class "Default")
      (node (ref "U$4") (pin "15") (pinfunction "PA1_15") (pintype "bidirectional"))
    )
    (net (code "51") (name "unconnected-(U$4-PA2{slash}UART2_TX-Pad16)") (class "Default")
      (node (ref "U$4") (pin "16") (pinfunction "PA2/UART2_TX_16") (pintype "bidirectional"))
    )
    (net (code "52") (name "unconnected-(U$4-PA3{slash}UART2_RX-Pad17)") (class "Default")
      (node (ref "U$4") (pin "17") (pinfunction "PA3/UART2_RX_17") (pintype "bidirectional"))
    )
    (net (code "53") (name "unconnected-(U$4-PA4{slash}SPI1_NSS-Pad20)") (class "Default")
      (node (ref "U$4") (pin "20") (pinfunction "PA4/SPI1_NSS_20") (pintype "bidirectional"))
    )
    (net (code "54") (name "unconnected-(U$4-PA5{slash}SPI1_SCK-Pad21)") (class "Default")
      (node (ref "U$4") (pin "21") (pinfunction "PA5/SPI1_SCK_21") (pintype "bidirectional"))
    )
    (net (code "55") (name "unconnected-(U$4-PA6{slash}SPI1_MISO-Pad22)") (class "Default")
      (node (ref "U$4") (pin "22") (pinfunction "PA6/SPI1_MISO_22") (pintype "bidirectional"))
    )
    (net (code "56") (name "unconnected-(U$4-PA7{slash}SPI1_MOSI-Pad23)") (class "Default")
      (node (ref "U$4") (pin "23") (pinfunction "PA7/SPI1_MOSI_23") (pintype "bidirectional"))
    )
    (net (code "57") (name "unconnected-(U$4-PA8-Pad41)") (class "Default")
      (node (ref "U$4") (pin "41") (pinfunction "PA8_41") (pintype "bidirectional"))
    )
    (net (code "58") (name "unconnected-(U$4-PA10{slash}UART1_RX-Pad43)") (class "Default")
      (node (ref "U$4") (pin "43") (pinfunction "PA10/UART1_RX_43") (pintype "bidirectional"))
    )
    (net (code "59") (name "unconnected-(U$4-PA13{slash}JTMS-Pad46)") (class "Default")
      (node (ref "U$4") (pin "46") (pinfunction "PA13/JTMS_46") (pintype "bidirectional"))
    )
    (net (code "60") (name "unconnected-(U$4-PA14{slash}JTCK-Pad49)") (class "Default")
      (node (ref "U$4") (pin "49") (pinfunction "PA14/JTCK_49") (pintype "bidirectional"))
    )
    (net (code "61") (name "unconnected-(U$4-PA15{slash}JTDI-Pad50)") (class "Default")
      (node (ref "U$4") (pin "50") (pinfunction "PA15/JTDI_50") (pintype "bidirectional"))
    )
    (net (code "62") (name "unconnected-(U$4-PB0-Pad26)") (class "Default")
      (node (ref "U$4") (pin "26") (pinfunction "PB0_26") (pintype "bidirectional"))
    )
    (net (code "63") (name "unconnected-(U$4-PB1-Pad27)") (class "Default")
      (node (ref "U$4") (pin "27") (pinfunction "PB1_27") (pintype "bidirectional"))
    )
    (net (code "64") (name "unconnected-(U$4-PB2-BOOT1-Pad28)") (class "Default")
      (node (ref "U$4") (pin "28") (pinfunction "PB2-BOOT1_28") (pintype "bidirectional"))
    )
    (net (code "65") (name "unconnected-(U$4-PB3{slash}JTDO-Pad55)") (class "Default")
      (node (ref "U$4") (pin "55") (pinfunction "PB3/JTDO_55") (pintype "bidirectional"))
    )
    (net (code "66") (name "unconnected-(U$4-PB4{slash}JTRST-Pad56)") (class "Default")
      (node (ref "U$4") (pin "56") (pinfunction "PB4/JTRST_56") (pintype "bidirectional"))
    )
    (net (code "67") (name "unconnected-(U$4-PB5-Pad57)") (class "Default")
      (node (ref "U$4") (pin "57") (pinfunction "PB5_57") (pintype "bidirectional"))
    )
    (net (code "68") (name "unconnected-(U$4-PB8-Pad61)") (class "Default")
      (node (ref "U$4") (pin "61") (pinfunction "PB8_61") (pintype "bidirectional"))
    )
    (net (code "69") (name "unconnected-(U$4-PB9-Pad62)") (class "Default")
      (node (ref "U$4") (pin "62") (pinfunction "PB9_62") (pintype "bidirectional"))
    )
    (net (code "70") (name "unconnected-(U$4-PB12{slash}I2S2_WS-Pad33)") (class "Default")
      (node (ref "U$4") (pin "33") (pinfunction "PB12/I2S2_WS_33") (pintype "bidirectional"))
    )
    (net (code "71") (name "unconnected-(U$4-PB13{slash}I2S2_CK-Pad34)") (class "Default")
      (node (ref "U$4") (pin "34") (pinfunction "PB13/I2S2_CK_34") (pintype "bidirectional"))
    )
    (net (code "72") (name "unconnected-(U$4-PB14{slash}I2S2_XD-Pad35)") (class "Default")
      (node (ref "U$4") (pin "35") (pinfunction "PB14/I2S2_XD_35") (pintype "bidirectional"))
    )
    (net (code "73") (name "unconnected-(U$4-PB15{slash}I2S2_SD-Pad36)") (class "Default")
      (node (ref "U$4") (pin "36") (pinfunction "PB15/I2S2_SD_36") (pintype "bidirectional"))
    )
    (net (code "74") (name "unconnected-(U$4-PC0-Pad8)") (class "Default")
      (node (ref "U$4") (pin "8") (pinfunction "PC0_8") (pintype "bidirectional"))
    )
    (net (code "75") (name "unconnected-(U$4-PC1-Pad9)") (class "Default")
      (node (ref "U$4") (pin "9") (pinfunction "PC1_9") (pintype "bidirectional"))
    )
    (net (code "76") (name "unconnected-(U$4-PC2-Pad10)") (class "Default")
      (node (ref "U$4") (pin "10") (pinfunction "PC2_10") (pintype "bidirectional"))
    )
    (net (code "77") (name "unconnected-(U$4-PC3-Pad11)") (class "Default")
      (node (ref "U$4") (pin "11") (pinfunction "PC3_11") (pintype "bidirectional"))
    )
    (net (code "78") (name "unconnected-(U$4-PC4-Pad24)") (class "Default")
      (node (ref "U$4") (pin "24") (pinfunction "PC4_24") (pintype "bidirectional"))
    )
    (net (code "79") (name "unconnected-(U$4-PC5-Pad25)") (class "Default")
      (node (ref "U$4") (pin "25") (pinfunction "PC5_25") (pintype "bidirectional"))
    )
    (net (code "80") (name "unconnected-(U$4-PC6{slash}I2S2_MCK-Pad37)") (class "Default")
      (node (ref "U$4") (pin "37") (pinfunction "PC6/I2S2_MCK_37") (pintype "bidirectional"))
    )
    (net (code "81") (name "unconnected-(U$4-PC7-Pad38)") (class "Default")
      (node (ref "U$4") (pin "38") (pinfunction "PC7_38") (pintype "bidirectional"))
    )
    (net (code "82") (name "unconnected-(U$4-PC8{slash}SDIO_D0-Pad39)") (class "Default")
      (node (ref "U$4") (pin "39") (pinfunction "PC8/SDIO_D0_39") (pintype "bidirectional"))
    )
    (net (code "83") (name "unconnected-(U$4-PC9{slash}SDIO_D1-Pad40)") (class "Default")
      (node (ref "U$4") (pin "40") (pinfunction "PC9/SDIO_D1_40") (pintype "bidirectional"))
    )
    (net (code "84") (name "unconnected-(U$4-PC10{slash}SDIO_D2-Pad51)") (class "Default")
      (node (ref "U$4") (pin "51") (pinfunction "PC10/SDIO_D2_51") (pintype "bidirectional"))
    )
    (net (code "85") (name "unconnected-(U$4-PC11{slash}SDIO_D3-Pad52)") (class "Default")
      (node (ref "U$4") (pin "52") (pinfunction "PC11/SDIO_D3_52") (pintype "bidirectional"))
    )
    (net (code "86") (name "unconnected-(U$4-PC12{slash}SDIO_CLK-Pad53)") (class "Default")
      (node (ref "U$4") (pin "53") (pinfunction "PC12/SDIO_CLK_53") (pintype "bidirectional"))
    )
    (net (code "87") (name "unconnected-(U$4-PC13-Pad2)") (class "Default")
      (node (ref "U$4") (pin "2") (pinfunction "PC13_2") (pintype "bidirectional"))
    )
    (net (code "88") (name "unconnected-(U$4-PD2{slash}SDIO_CMD-Pad54)") (class "Default")
      (node (ref "U$4") (pin "54") (pinfunction "PD2/SDIO_CMD_54") (pintype "bidirectional"))
    )
    (net (code "89") (name "unconnected-(U$4-VBAT-Pad1)") (class "Default")
      (node (ref "U$4") (pin "1") (pinfunction "VBAT_1") (pintype "bidirectional"))
    )
  )
)
